# spring.net
KiCad netlist of a schematic drawn in EAGLE
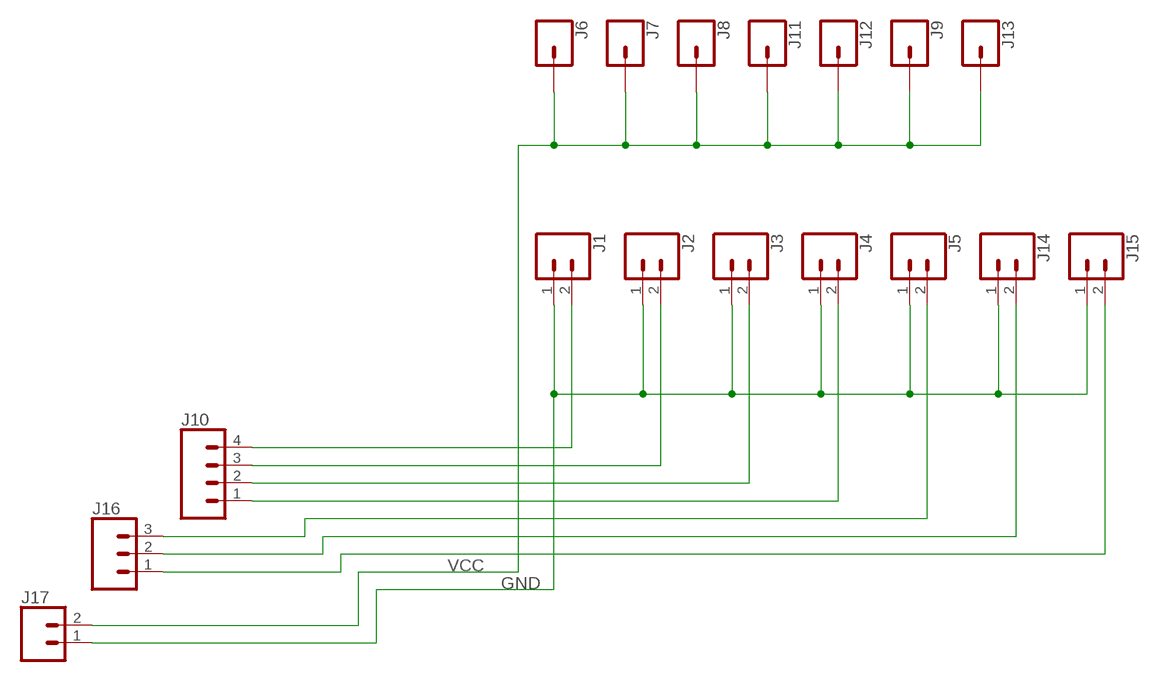
[diagram p0: schematic, sheet 1]

(export (version "E")
  (design (tool "Eeschema 10.0.6"))
  (components
    (comp (ref "J1")
      (value "CONN_02")
      (footprint "eagle-import:1X02")
      (libsource (lib "eagle-import") (part "CONN_02"))
    )
    (comp (ref "J2")
      (value "CONN_02")
      (footprint "eagle-import:1X02")
      (libsource (lib "eagle-import") (part "CONN_02"))
    )
    (comp (ref "J3")
      (value "CONN_02")
      (footprint "eagle-import:1X02")
      (libsource (lib "eagle-import") (part "CONN_02"))
    )
    (comp (ref "J4")
      (value "CONN_02")
      (footprint "eagle-import:1X02")
      (libsource (lib "eagle-import") (part "CONN_02"))
    )
    (comp (ref "J5")
      (value "CONN_02")
      (footprint "eagle-import:1X02")
      (libsource (lib "eagle-import") (part "CONN_02"))
    )
    (comp (ref "J6")
      (value "CONN_01OFFSET")
      (footprint "eagle-import:1X01_OFFSET")
      (libsource (lib "eagle-import") (part "CONN_01OFFSET"))
    )
    (comp (ref "J7")
      (value "CONN_01OFFSET")
      (footprint "eagle-import:1X01_OFFSET")
      (libsource (lib "eagle-import") (part "CONN_01OFFSET"))
    )
    (comp (ref "J8")
      (value "CONN_01OFFSET")
      (footprint "eagle-import:1X01_OFFSET")
      (libsource (lib "eagle-import") (part "CONN_01OFFSET"))
    )
    (comp (ref "J9")
      (value "CONN_01OFFSET")
      (footprint "eagle-import:1X01_OFFSET")
      (libsource (lib "eagle-import") (part "CONN_01OFFSET"))
    )
    (comp (ref "J10")
      (value "CONN_04")
      (footprint "eagle-import:1X04")
      (libsource (lib "eagle-import") (part "CONN_04"))
    )
    (comp (ref "J11")
      (value "CONN_01OFFSET")
      (footprint "eagle-import:1X01_OFFSET")
      (libsource (lib "eagle-import") (part "CONN_01OFFSET"))
    )
    (comp (ref "J12")
      (value "CONN_01OFFSET")
      (footprint "eagle-import:1X01_OFFSET")
      (libsource (lib "eagle-import") (part "CONN_01OFFSET"))
    )
    (comp (ref "J13")
      (value "CONN_01OFFSET")
      (footprint "eagle-import:1X01_OFFSET")
      (libsource (lib "eagle-import") (part "CONN_01OFFSET"))
    )
    (comp (ref "J14")
      (value "CONN_02")
      (footprint "eagle-import:1X02")
      (libsource (lib "eagle-import") (part "CONN_02"))
    )
    (comp (ref "J15")
      (value "CONN_02")
      (footprint "eagle-import:1X02")
      (libsource (lib "eagle-import") (part "CONN_02"))
    )
    (comp (ref "J16")
      (value "CONN_03")
      (footprint "eagle-import:1X03")
      (libsource (lib "eagle-import") (part "CONN_03"))
    )
    (comp (ref "J17")
      (value "CONN_02")
      (footprint "eagle-import:1X02")
      (libsource (lib "eagle-import") (part "CONN_02"))
    )
  )
  (nets
    (net (code "1") (name "/GND") (class "Default")
      (node (ref "J1") (pin "1") (pinfunction "1_1") (pintype "passive"))
      (node (ref "J14") (pin "1") (pinfunction "1_1") (pintype "passive"))
      (node (ref "J15") (pin "1") (pinfunction "1_1") (pintype "passive"))
      (node (ref "J17") (pin "1") (pinfunction "1_1") (pintype "passive"))
      (node (ref "J2") (pin "1") (pinfunction "1_1") (pintype "passive"))
      (node (ref "J3") (pin "1") (pinfunction "1_1") (pintype "passive"))
      (node (ref "J4") (pin "1") (pinfunction "1_1") (pintype "passive"))
      (node (ref "J5") (pin "1") (pinfunction "1_1") (pintype "passive"))
    )
    (net (code "2") (name "/VCC") (class "Default")
      (node (ref "J11") (pin "1") (pinfunction "1_1") (pintype "passive"))
      (node (ref "J12") (pin "1") (pinfunction "1_1") (pintype "passive"))
      (node (ref "J13") (pin "1") (pinfunction "1_1") (pintype "passive"))
      (node (ref "J17") (pin "2") (pinfunction "2_2") (pintype "passive"))
      (node (ref "J6") (pin "1") (pinfunction "1_1") (pintype "passive"))
      (node (ref "J7") (pin "1") (pinfunction "1_1") (pintype "passive"))
      (node (ref "J8") (pin "1") (pinfunction "1_1") (pintype "passive"))
      (node (ref "J9") (pin "1") (pinfunction "1_1") (pintype "passive"))
    )
    (net (code "3") (name "Net-(J1-Pad2)") (class "Default")
      (node (ref "J1") (pin "2") (pinfunction "2_2") (pintype "passive"))
      (node (ref "J10") (pin "4") (pinfunction "4_4") (pintype "passive"))
    )
    (net (code "4") (name "Net-(J10-Pad1)") (class "Default")
      (node (ref "J10") (pin "1") (pinfunction "1_1") (pintype "passive"))
      (node (ref "J4") (pin "2") (pinfunction "2_2") (pintype "passive"))
    )
    (net (code "5") (name "Net-(J10-Pad2)") (class "Default")
      (node (ref "J10") (pin "2") (pinfunction "2_2") (pintype "passive"))
      (node (ref "J3") (pin "2") (pinfunction "2_2") (pintype "passive"))
    )
    (net (code "6") (name "Net-(J10-Pad3)") (class "Default")
      (node (ref "J10") (pin "3") (pinfunction "3_3") (pintype "passive"))
      (node (ref "J2") (pin "2") (pinfunction "2_2") (pintype "passive"))
    )
    (net (code "7") (name "Net-(J14-Pad2)") (class "Default")
      (node (ref "J14") (pin "2") (pinfunction "2_2") (pintype "passive"))
      (node (ref "J16") (pin "2") (pinfunction "2_2") (pintype "passive"))
    )
    (net (code "8") (name "Net-(J15-Pad2)") (class "Default")
      (node (ref "J15") (pin "2") (pinfunction "2_2") (pintype "passive"))
      (node (ref "J16") (pin "1") (pinfunction "1_1") (pintype "passive"))
    )
    (net (code "9") (name "Net-(J16-Pad3)") (class "Default")
      (node (ref "J16") (pin "3") (pinfunction "3_3") (pintype "passive"))
      (node (ref "J5") (pin "2") (pinfunction "2_2") (pintype "passive"))
    )
  )
)
